# Grove_-_2-Coil_Latching_Relay_v1.net
KiCad netlist of a schematic drawn in EAGLE
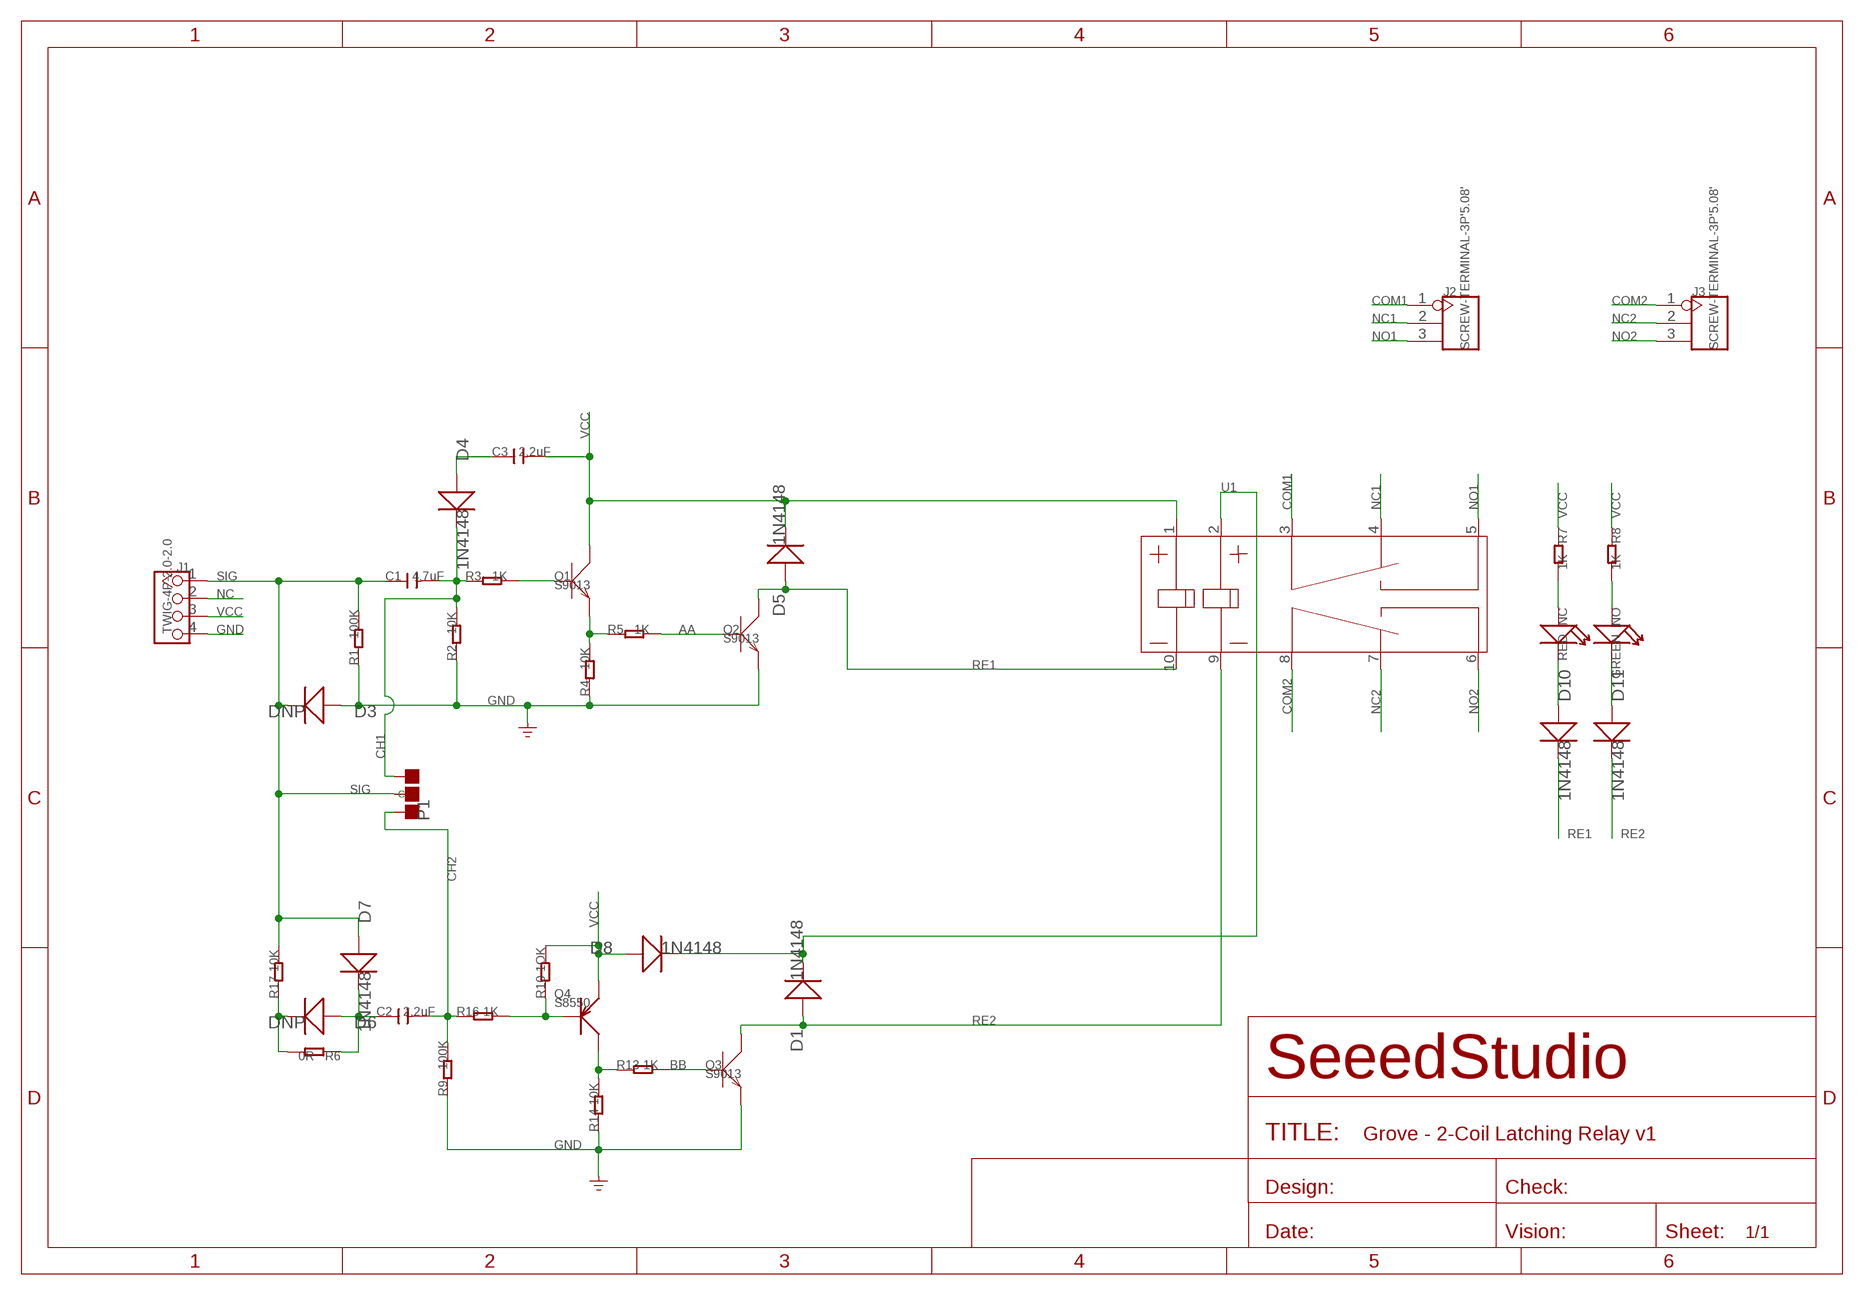
[diagram p0: schematic, sheet 1]

(export (version "E")
  (design (tool "Eeschema 10.0.6"))
  (components
    (comp (ref "C1")
      (value "4.7uF")
      (footprint "eagle-import:C0805")
      (libsource (lib "eagle-import") (part "C-0805"))
    )
    (comp (ref "C2")
      (value "2.2uF")
      (footprint "eagle-import:C0805")
      (libsource (lib "eagle-import") (part "C-0805"))
    )
    (comp (ref "C3")
      (value "2.2uF")
      (footprint "eagle-import:C0805")
      (libsource (lib "eagle-import") (part "C-0805"))
    )
    (comp (ref "D1")
      (value "1N4148")
      (footprint "eagle-import:DO-35-SMD")
      (libsource (lib "eagle-import") (part "D'1N4148-SMD'"))
    )
    (comp (ref "D3")
      (value "DNP")
      (footprint "eagle-import:DO-35-SMD")
      (libsource (lib "eagle-import") (part "D'1N4148-SMD'"))
    )
    (comp (ref "D4")
      (value "1N4148")
      (footprint "eagle-import:DO-35-SMD")
      (libsource (lib "eagle-import") (part "D'1N4148-SMD'"))
    )
    (comp (ref "D5")
      (value "1N4148")
      (footprint "eagle-import:DO-35-SMD")
      (libsource (lib "eagle-import") (part "D'1N4148-SMD'"))
    )
    (comp (ref "D6")
      (value "DNP")
      (footprint "eagle-import:DO-35-SMD")
      (libsource (lib "eagle-import") (part "D'1N4148-SMD'"))
    )
    (comp (ref "D7")
      (value "1N4148")
      (footprint "eagle-import:DO-35-SMD")
      (libsource (lib "eagle-import") (part "D'1N4148-SMD'"))
    )
    (comp (ref "D8")
      (value "1N4148")
      (footprint "eagle-import:DO-35-SMD")
      (libsource (lib "eagle-import") (part "D'1N4148-SMD'"))
    )
    (comp (ref "D10")
      (value "1N4148")
      (footprint "eagle-import:DO-35-SMD")
      (libsource (lib "eagle-import") (part "D'1N4148-SMD'"))
    )
    (comp (ref "D11")
      (value "1N4148")
      (footprint "eagle-import:DO-35-SMD")
      (libsource (lib "eagle-import") (part "D'1N4148-SMD'"))
    )
    (comp (ref "J1")
      (value "TWIG-4P-2.0-2.0")
      (footprint "eagle-import:4P-2.0")
      (libsource (lib "eagle-import") (part "TWIG-4P-2.0-2.0"))
    )
    (comp (ref "J2")
      (value "SCREW-TERMINAL-3P'5.08'")
      (footprint "eagle-import:3P-5.08")
      (libsource (lib "eagle-import") (part "SCREW-TERMINAL-3P'5.08'"))
    )
    (comp (ref "J3")
      (value "SCREW-TERMINAL-3P'5.08'")
      (footprint "eagle-import:3P-5.08")
      (libsource (lib "eagle-import") (part "SCREW-TERMINAL-3P'5.08'"))
    )
    (comp (ref "NC")
      (value "RED")
      (footprint "eagle-import:LED-0603")
      (libsource (lib "eagle-import") (part "LED'0603'"))
    )
    (comp (ref "NO")
      (value "GREEN")
      (footprint "eagle-import:LED-0603")
      (libsource (lib "eagle-import") (part "LED'0603'"))
    )
    (comp (ref "P1")
      (value "PAD-JUMPER-3P-40*40")
      (footprint "eagle-import:3P-SMD-4.1X1.5")
      (fields (field (name "PARTNO") "DNP"))
      (libsource (lib "eagle-import") (part "PAD-JUMPER-3P-4040"))
    )
    (comp (ref "Q1")
      (value "S9013")
      (footprint "eagle-import:SOT23")
      (libsource (lib "eagle-import") (part "TRANSISTOR-NPN-SOT23"))
    )
    (comp (ref "Q2")
      (value "S9013")
      (footprint "eagle-import:SOT23")
      (libsource (lib "eagle-import") (part "TRANSISTOR-NPN-SOT23"))
    )
    (comp (ref "Q3")
      (value "S9013")
      (footprint "eagle-import:SOT23")
      (libsource (lib "eagle-import") (part "TRANSISTOR-NPN-SOT23"))
    )
    (comp (ref "Q4")
      (value "S8550")
      (footprint "eagle-import:SOT23")
      (libsource (lib "eagle-import") (part "TRANSISTOR-PNP-SOT23"))
    )
    (comp (ref "R1")
      (value "100K")
      (footprint "eagle-import:R0603")
      (libsource (lib "eagle-import") (part "R-0603"))
    )
    (comp (ref "R2")
      (value "10K")
      (footprint "eagle-import:R0603")
      (libsource (lib "eagle-import") (part "R-0603"))
    )
    (comp (ref "R3")
      (value "1K")
      (footprint "eagle-import:R0603")
      (libsource (lib "eagle-import") (part "R-0603"))
    )
    (comp (ref "R4")
      (value "10K")
      (footprint "eagle-import:R0603")
      (libsource (lib "eagle-import") (part "R-0603"))
    )
    (comp (ref "R5")
      (value "1K")
      (footprint "eagle-import:R0603")
      (libsource (lib "eagle-import") (part "R-0603"))
    )
    (comp (ref "R6")
      (value "0R")
      (footprint "eagle-import:R0603")
      (libsource (lib "eagle-import") (part "R-0603"))
    )
    (comp (ref "R7")
      (value "1K")
      (footprint "eagle-import:R0603")
      (libsource (lib "eagle-import") (part "R-0603"))
    )
    (comp (ref "R8")
      (value "1K")
      (footprint "eagle-import:R0603")
      (libsource (lib "eagle-import") (part "R-0603"))
    )
    (comp (ref "R9")
      (value "100K")
      (footprint "eagle-import:R0603")
      (libsource (lib "eagle-import") (part "R-0603"))
    )
    (comp (ref "R10")
      (value "1OK")
      (footprint "eagle-import:R0603")
      (libsource (lib "eagle-import") (part "R-0603"))
    )
    (comp (ref "R13")
      (value "1K")
      (footprint "eagle-import:R0603")
      (libsource (lib "eagle-import") (part "R-0603"))
    )
    (comp (ref "R14")
      (value "10K")
      (footprint "eagle-import:R0603")
      (libsource (lib "eagle-import") (part "R-0603"))
    )
    (comp (ref "R16")
      (value "1K")
      (footprint "eagle-import:R0603")
      (libsource (lib "eagle-import") (part "R-0603"))
    )
    (comp (ref "R17")
      (value "10K")
      (footprint "eagle-import:R0603")
      (libsource (lib "eagle-import") (part "R-0603"))
    )
    (comp (ref "U1")
      (value "RELAY-HFD2/005-S-L2'HFD2/005-S-L2'")
      (footprint "eagle-import:10P-20.2X10.2X10.6")
      (libsource (lib "eagle-import") (part "RELAY-HFD2/005-S-L2'HFD2/005-S-L2'"))
    )
  )
  (nets
    (net (code "1") (name "/AA") (class "Default")
      (node (ref "Q2") (pin "1") (pinfunction "B_1") (pintype "passive"))
      (node (ref "R5") (pin "2") (pinfunction "2_2") (pintype "passive"))
    )
    (net (code "2") (name "/BB") (class "Default")
      (node (ref "Q3") (pin "1") (pinfunction "B_1") (pintype "passive"))
      (node (ref "R13") (pin "2") (pinfunction "2_2") (pintype "passive"))
    )
    (net (code "3") (name "/CH1") (class "Default")
      (node (ref "C1") (pin "2") (pinfunction "2_2") (pintype "passive"))
      (node (ref "D4") (pin "C") (pinfunction "-_C") (pintype "passive"))
      (node (ref "P1") (pin "00") (pinfunction "L_00") (pintype "bidirectional"))
      (node (ref "R2") (pin "2") (pinfunction "2_2") (pintype "passive"))
      (node (ref "R3") (pin "1") (pinfunction "1_1") (pintype "passive"))
    )
    (net (code "4") (name "/CH2") (class "Default")
      (node (ref "C2") (pin "2") (pinfunction "2_2") (pintype "passive"))
      (node (ref "P1") (pin "11") (pinfunction "R_11") (pintype "bidirectional"))
      (node (ref "R16") (pin "1") (pinfunction "1_1") (pintype "passive"))
      (node (ref "R9") (pin "2") (pinfunction "2_2") (pintype "passive"))
    )
    (net (code "5") (name "/COM1") (class "Default")
      (node (ref "J2") (pin "1") (pinfunction "P$1_1") (pintype "bidirectional"))
      (node (ref "U1") (pin "3") (pinfunction "4_3") (pintype "bidirectional"))
    )
    (net (code "6") (name "/COM2") (class "Default")
      (node (ref "J3") (pin "1") (pinfunction "P$1_1") (pintype "bidirectional"))
      (node (ref "U1") (pin "8") (pinfunction "13_8") (pintype "bidirectional"))
    )
    (net (code "7") (name "/NC") (class "Default")
      (node (ref "J1") (pin "2") (pinfunction "2_2") (pintype "bidirectional"))
    )
    (net (code "8") (name "/NC1") (class "Default")
      (node (ref "J2") (pin "2") (pinfunction "P$2_2") (pintype "bidirectional"))
      (node (ref "U1") (pin "4") (pinfunction "6_4") (pintype "bidirectional"))
    )
    (net (code "9") (name "/NC2") (class "Default")
      (node (ref "J3") (pin "2") (pinfunction "P$2_2") (pintype "bidirectional"))
      (node (ref "U1") (pin "7") (pinfunction "11_7") (pintype "bidirectional"))
    )
    (net (code "10") (name "/NO1") (class "Default")
      (node (ref "J2") (pin "3") (pinfunction "P$3_3") (pintype "bidirectional"))
      (node (ref "U1") (pin "5") (pinfunction "8_5") (pintype "bidirectional"))
    )
    (net (code "11") (name "/NO2") (class "Default")
      (node (ref "J3") (pin "3") (pinfunction "P$3_3") (pintype "bidirectional"))
      (node (ref "U1") (pin "6") (pinfunction "9_6") (pintype "bidirectional"))
    )
    (net (code "12") (name "/RE1") (class "Default")
      (node (ref "D10") (pin "C") (pinfunction "-_C") (pintype "passive"))
      (node (ref "D5") (pin "A") (pinfunction "+_A") (pintype "passive"))
      (node (ref "Q2") (pin "3") (pinfunction "C_3") (pintype "passive"))
      (node (ref "U1") (pin "10") (pinfunction "16_10") (pintype "bidirectional"))
    )
    (net (code "13") (name "/RE2") (class "Default")
      (node (ref "D1") (pin "A") (pinfunction "+_A") (pintype "passive"))
      (node (ref "D11") (pin "C") (pinfunction "-_C") (pintype "passive"))
      (node (ref "Q3") (pin "3") (pinfunction "C_3") (pintype "passive"))
      (node (ref "U1") (pin "9") (pinfunction "15_9") (pintype "bidirectional"))
    )
    (net (code "14") (name "/SIG") (class "Default")
      (node (ref "C1") (pin "1") (pinfunction "1_1") (pintype "passive"))
      (node (ref "D3") (pin "C") (pinfunction "-_C") (pintype "passive"))
      (node (ref "D7") (pin "A") (pinfunction "+_A") (pintype "passive"))
      (node (ref "J1") (pin "1") (pinfunction "1_1") (pintype "bidirectional"))
      (node (ref "P1") (pin "MM") (pinfunction "C_MM") (pintype "bidirectional"))
      (node (ref "R1") (pin "2") (pinfunction "2_2") (pintype "passive"))
      (node (ref "R17") (pin "2") (pinfunction "2_2") (pintype "passive"))
    )
    (net (code "15") (name "/VCC") (class "Default")
      (node (ref "C3") (pin "2") (pinfunction "2_2") (pintype "passive"))
      (node (ref "D5") (pin "C") (pinfunction "-_C") (pintype "passive"))
      (node (ref "D8") (pin "A") (pinfunction "+_A") (pintype "passive"))
      (node (ref "J1") (pin "3") (pinfunction "3_3") (pintype "bidirectional"))
      (node (ref "Q1") (pin "3") (pinfunction "C_3") (pintype "passive"))
      (node (ref "Q4") (pin "2") (pinfunction "E_2") (pintype "passive"))
      (node (ref "R10") (pin "2") (pinfunction "2_2") (pintype "passive"))
      (node (ref "R7") (pin "1") (pinfunction "1_1") (pintype "passive"))
      (node (ref "R8") (pin "1") (pinfunction "1_1") (pintype "passive"))
      (node (ref "U1") (pin "1") (pinfunction "1_1") (pintype "bidirectional"))
    )
    (net (code "16") (name "GND_POWER") (class "Default")
      (node (ref "D3") (pin "A") (pinfunction "+_A") (pintype "passive"))
      (node (ref "J1") (pin "4") (pinfunction "4_4") (pintype "bidirectional"))
      (node (ref "Q2") (pin "2") (pinfunction "E_2") (pintype "passive"))
      (node (ref "Q3") (pin "2") (pinfunction "E_2") (pintype "passive"))
      (node (ref "R1") (pin "1") (pinfunction "1_1") (pintype "passive"))
      (node (ref "R14") (pin "1") (pinfunction "1_1") (pintype "passive"))
      (node (ref "R2") (pin "1") (pinfunction "1_1") (pintype "passive"))
      (node (ref "R4") (pin "1") (pinfunction "1_1") (pintype "passive"))
      (node (ref "R9") (pin "1") (pinfunction "1_1") (pintype "passive"))
    )
    (net (code "17") (name "Net-(D1--)") (class "Default")
      (node (ref "D1") (pin "C") (pinfunction "-_C") (pintype "passive"))
      (node (ref "D8") (pin "C") (pinfunction "-_C") (pintype "passive"))
      (node (ref "U1") (pin "2") (pinfunction "2_2") (pintype "bidirectional"))
    )
    (net (code "18") (name "Net-(D4-+)") (class "Default")
      (node (ref "C3") (pin "1") (pinfunction "1_1") (pintype "passive"))
      (node (ref "D4") (pin "A") (pinfunction "+_A") (pintype "passive"))
    )
    (net (code "19") (name "Net-(D6-+)") (class "Default")
      (node (ref "C2") (pin "1") (pinfunction "1_1") (pintype "passive"))
      (node (ref "D6") (pin "A") (pinfunction "+_A") (pintype "passive"))
      (node (ref "D7") (pin "C") (pinfunction "-_C") (pintype "passive"))
      (node (ref "R6") (pin "1") (pinfunction "1_1") (pintype "passive"))
    )
    (net (code "20") (name "Net-(D6--)") (class "Default")
      (node (ref "D6") (pin "C") (pinfunction "-_C") (pintype "passive"))
      (node (ref "R17") (pin "1") (pinfunction "1_1") (pintype "passive"))
      (node (ref "R6") (pin "2") (pinfunction "2_2") (pintype "passive"))
    )
    (net (code "21") (name "Net-(D10-+)") (class "Default")
      (node (ref "D10") (pin "A") (pinfunction "+_A") (pintype "passive"))
      (node (ref "NC") (pin "-") (pinfunction "-_-") (pintype "passive"))
    )
    (net (code "22") (name "Net-(D11-+)") (class "Default")
      (node (ref "D11") (pin "A") (pinfunction "+_A") (pintype "passive"))
      (node (ref "NO") (pin "-") (pinfunction "-_-") (pintype "passive"))
    )
    (net (code "23") (name "Net-(NC-Pad+)") (class "Default")
      (node (ref "NC") (pin "+") (pinfunction "+_+") (pintype "passive"))
      (node (ref "R7") (pin "2") (pinfunction "2_2") (pintype "passive"))
    )
    (net (code "24") (name "Net-(NO-Pad+)") (class "Default")
      (node (ref "NO") (pin "+") (pinfunction "+_+") (pintype "passive"))
      (node (ref "R8") (pin "2") (pinfunction "2_2") (pintype "passive"))
    )
    (net (code "25") (name "Net-(Q1-B)") (class "Default")
      (node (ref "Q1") (pin "1") (pinfunction "B_1") (pintype "passive"))
      (node (ref "R3") (pin "2") (pinfunction "2_2") (pintype "passive"))
    )
    (net (code "26") (name "Net-(Q1-E)") (class "Default")
      (node (ref "Q1") (pin "2") (pinfunction "E_2") (pintype "passive"))
      (node (ref "R4") (pin "2") (pinfunction "2_2") (pintype "passive"))
      (node (ref "R5") (pin "1") (pinfunction "1_1") (pintype "passive"))
    )
    (net (code "27") (name "Net-(Q4-B)") (class "Default")
      (node (ref "Q4") (pin "1") (pinfunction "B_1") (pintype "passive"))
      (node (ref "R10") (pin "1") (pinfunction "1_1") (pintype "passive"))
      (node (ref "R16") (pin "2") (pinfunction "2_2") (pintype "passive"))
    )
    (net (code "28") (name "Net-(Q4-C)") (class "Default")
      (node (ref "Q4") (pin "3") (pinfunction "C_3") (pintype "passive"))
      (node (ref "R13") (pin "1") (pinfunction "1_1") (pintype "passive"))
      (node (ref "R14") (pin "2") (pinfunction "2_2") (pintype "passive"))
    )
  )
)
